# attiny13breadhead.net
KiCad netlist of a schematic drawn in EAGLE
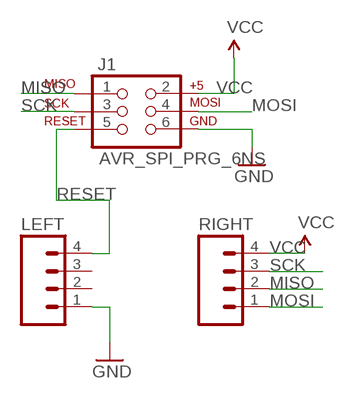
[diagram p0: schematic, sheet 1]

(export (version "E")
  (design (tool "Eeschema 10.0.6"))
  (components
    (comp (ref "J1")
      (value "AVR_SPI_PRG_6NS")
      (footprint "eagle-import:2X3-NS")
      (libsource (lib "eagle-import") (part "AVR_SPI_PRG_6NS"))
    )
    (comp (ref "LEFT")
      (value "M04PTH")
      (footprint "eagle-import:1X04")
      (libsource (lib "eagle-import") (part "M04PTH"))
    )
    (comp (ref "RIGHT")
      (value "M04PTH")
      (footprint "eagle-import:1X04")
      (libsource (lib "eagle-import") (part "M04PTH"))
    )
  )
  (nets
    (net (code "1") (name "/MISO") (class "Default")
      (node (ref "J1") (pin "1") (pinfunction "1_1") (pintype "passive"))
      (node (ref "RIGHT") (pin "2") (pinfunction "2_2") (pintype "passive"))
    )
    (net (code "2") (name "/MOSI") (class "Default")
      (node (ref "J1") (pin "4") (pinfunction "4_4") (pintype "passive"))
      (node (ref "RIGHT") (pin "1") (pinfunction "1_1") (pintype "passive"))
    )
    (net (code "3") (name "/RESET") (class "Default")
      (node (ref "J1") (pin "5") (pinfunction "5_5") (pintype "passive"))
      (node (ref "LEFT") (pin "4") (pinfunction "4_4") (pintype "passive"))
    )
    (net (code "4") (name "/SCK") (class "Default")
      (node (ref "J1") (pin "3") (pinfunction "3_3") (pintype "passive"))
      (node (ref "RIGHT") (pin "3") (pinfunction "3_3") (pintype "passive"))
    )
    (net (code "5") (name "GND") (class "Default")
      (node (ref "J1") (pin "6") (pinfunction "6_6") (pintype "passive"))
      (node (ref "LEFT") (pin "1") (pinfunction "1_1") (pintype "passive"))
    )
    (net (code "6") (name "VCC") (class "Default")
      (node (ref "J1") (pin "2") (pinfunction "2_2") (pintype "passive"))
      (node (ref "RIGHT") (pin "4") (pinfunction "4_4") (pintype "passive"))
    )
    (net (code "7") (name "unconnected-(LEFT-Pad2)") (class "Default")
      (node (ref "LEFT") (pin "2") (pinfunction "2_2") (pintype "passive"))
    )
    (net (code "8") (name "unconnected-(LEFT-Pad3)") (class "Default")
      (node (ref "LEFT") (pin "3") (pinfunction "3_3") (pintype "passive"))
    )
  )
)
